# 03_Mechanicals.net
KiCad netlist of a schematic drawn in Altium Designer
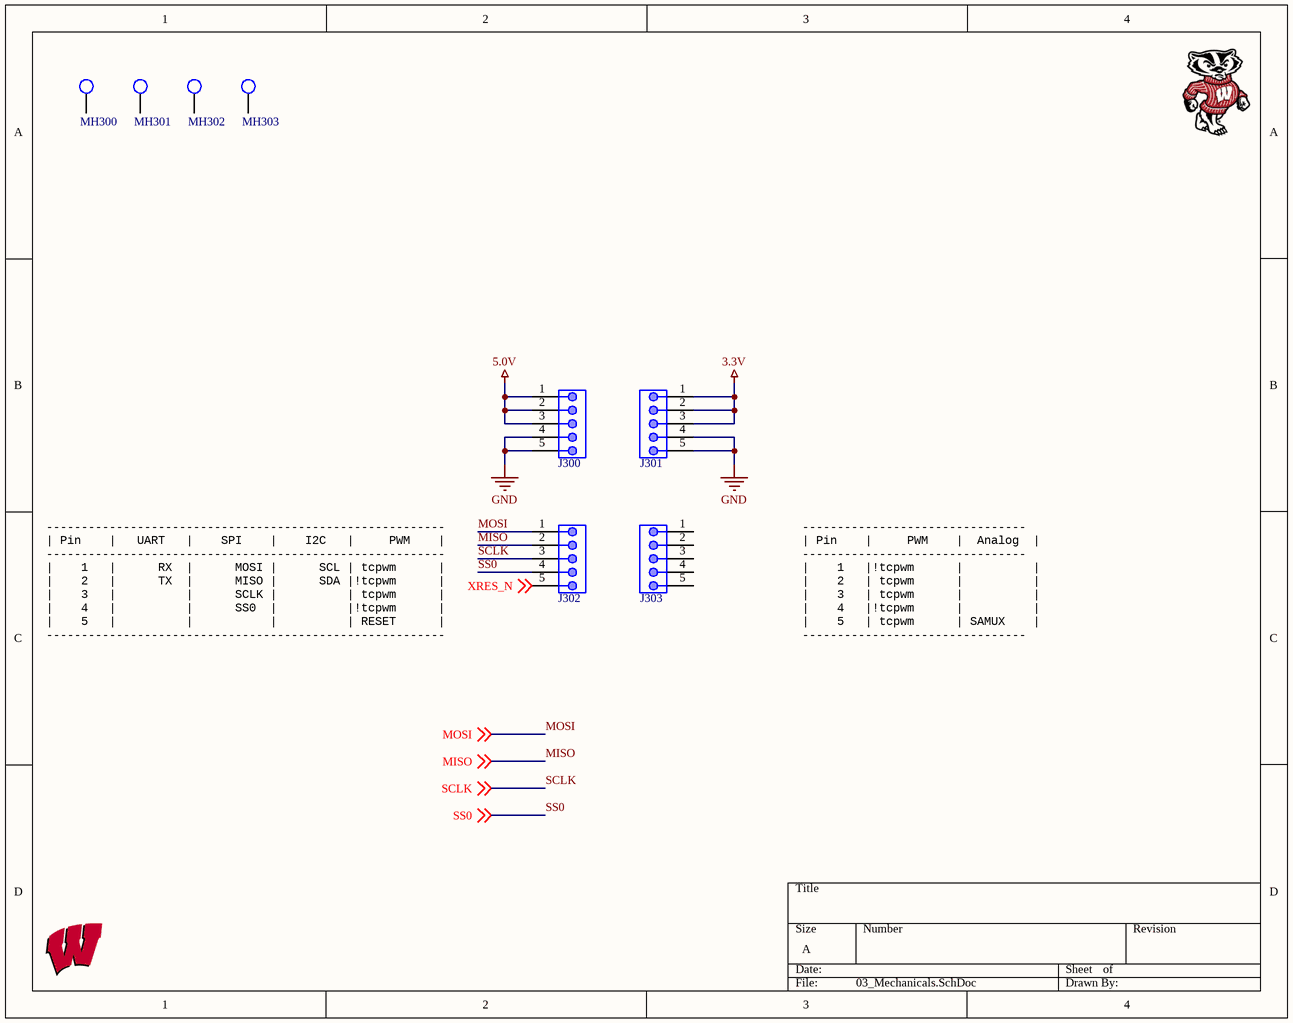
[diagram p0: 03_Mechanicals.SchDoc]

(export (version "E")
  (design (tool "Eeschema 10.0.6"))
  (components
    (comp (ref "J300")
      (value "CONN_HEADER_MALE_1x5")
      (footprint "HDR1X5")
      (description "Header, 5-Pin")
      (libsource (lib "Connectors") (part "CONN_HEADER_MALE_1x5"))
    )
    (comp (ref "J301")
      (value "CONN_HEADER_MALE_1x5")
      (footprint "HDR1X5")
      (description "Header, 5-Pin")
      (libsource (lib "") (part "CONN_HEADER_MALE_1x5_1"))
    )
    (comp (ref "J302")
      (value "CONN_HEADER_MALE_1x5")
      (footprint "HDR1X5")
      (description "Header, 5-Pin")
      (libsource (lib "Connectors") (part "CONN_HEADER_MALE_1x5"))
    )
    (comp (ref "J303")
      (value "CONN_HEADER_MALE_1x5")
      (footprint "HDR1X5")
      (description "Header, 5-Pin")
      (libsource (lib "") (part "CONN_HEADER_MALE_1x5_1"))
    )
    (comp (ref "MH300")
      (value "MHOLE_2_55MM")
      (footprint "MHOLE_2_55MM")
      (description "Mounting Holde")
      (fields (field (name "MANUFACTURER PART NUMBER") "UW MTHOLE"))
      (libsource (lib "ece315-2018-fall") (part "MHOLE_2_55MM"))
    )
    (comp (ref "MH301")
      (value "MHOLE_2_55MM")
      (footprint "MHOLE_2_55MM")
      (description "Mounting Holde")
      (fields (field (name "MANUFACTURER PART NUMBER") "UW MTHOLE"))
      (libsource (lib "ece315-2018-fall") (part "MHOLE_2_55MM"))
    )
    (comp (ref "MH302")
      (value "MHOLE_2_55MM")
      (footprint "MHOLE_2_55MM")
      (description "Mounting Holde")
      (fields (field (name "MANUFACTURER PART NUMBER") "UW MTHOLE"))
      (libsource (lib "ece315-2018-fall") (part "MHOLE_2_55MM"))
    )
    (comp (ref "MH303")
      (value "MHOLE_2_55MM")
      (footprint "MHOLE_2_55MM")
      (description "Mounting Holde")
      (fields (field (name "MANUFACTURER PART NUMBER") "UW MTHOLE"))
      (libsource (lib "ece315-2018-fall") (part "MHOLE_2_55MM"))
    )
  )
  (nets
    (net (code "1") (name "3.3V") (class "Default")
      (node (ref "J301") (pin "1") (pinfunction "1_1") (pintype "passive"))
      (node (ref "J301") (pin "2") (pinfunction "2_2") (pintype "passive"))
      (node (ref "J301") (pin "3") (pinfunction "3_3") (pintype "passive"))
    )
    (net (code "2") (name "5.0V") (class "Default")
      (node (ref "J300") (pin "1") (pinfunction "1_1") (pintype "passive"))
      (node (ref "J300") (pin "2") (pinfunction "2_2") (pintype "passive"))
      (node (ref "J300") (pin "3") (pinfunction "3_3") (pintype "passive"))
    )
    (net (code "3") (name "GND") (class "Default")
      (node (ref "J300") (pin "4") (pinfunction "4_4") (pintype "passive"))
      (node (ref "J300") (pin "5") (pinfunction "5_5") (pintype "passive"))
      (node (ref "J301") (pin "4") (pinfunction "4_4") (pintype "passive"))
      (node (ref "J301") (pin "5") (pinfunction "5_5") (pintype "passive"))
    )
    (net (code "4") (name "MISO") (class "Default")
      (node (ref "J302") (pin "2") (pinfunction "2_2") (pintype "passive"))
    )
    (net (code "5") (name "MOSI") (class "Default")
      (node (ref "J302") (pin "1") (pinfunction "1_1") (pintype "passive"))
    )
    (net (code "6") (name "SCLK") (class "Default")
      (node (ref "J302") (pin "3") (pinfunction "3_3") (pintype "passive"))
    )
    (net (code "7") (name "SS0") (class "Default")
      (node (ref "J302") (pin "4") (pinfunction "4_4") (pintype "passive"))
    )
    (net (code "8") (name "XRES_N") (class "Default")
      (node (ref "J302") (pin "5") (pinfunction "5_5") (pintype "passive"))
    )
    (net (code "9") (name "unconnected-(J303-Pad1)") (class "Default")
      (node (ref "J303") (pin "1") (pinfunction "1_1") (pintype "passive"))
    )
    (net (code "10") (name "unconnected-(J303-Pad2)") (class "Default")
      (node (ref "J303") (pin "2") (pinfunction "2_2") (pintype "passive"))
    )
    (net (code "11") (name "unconnected-(J303-Pad3)") (class "Default")
      (node (ref "J303") (pin "3") (pinfunction "3_3") (pintype "passive"))
    )
    (net (code "12") (name "unconnected-(J303-Pad4)") (class "Default")
      (node (ref "J303") (pin "4") (pinfunction "4_4") (pintype "passive"))
    )
    (net (code "13") (name "unconnected-(J303-Pad5)") (class "Default")
      (node (ref "J303") (pin "5") (pinfunction "5_5") (pintype "passive"))
    )
    (net (code "14") (name "unconnected-(MH300-Pad1)") (class "Default")
      (node (ref "MH300") (pin "1") (pintype "passive"))
    )
    (net (code "15") (name "unconnected-(MH301-Pad1)") (class "Default")
      (node (ref "MH301") (pin "1") (pintype "passive"))
    )
    (net (code "16") (name "unconnected-(MH302-Pad1)") (class "Default")
      (node (ref "MH302") (pin "1") (pintype "passive"))
    )
    (net (code "17") (name "unconnected-(MH303-Pad1)") (class "Default")
      (node (ref "MH303") (pin "1") (pintype "passive"))
    )
  )
)
